# BMW_E34_Start-Stop_Btn.net
KiCad netlist of a schematic drawn in Altium Designer
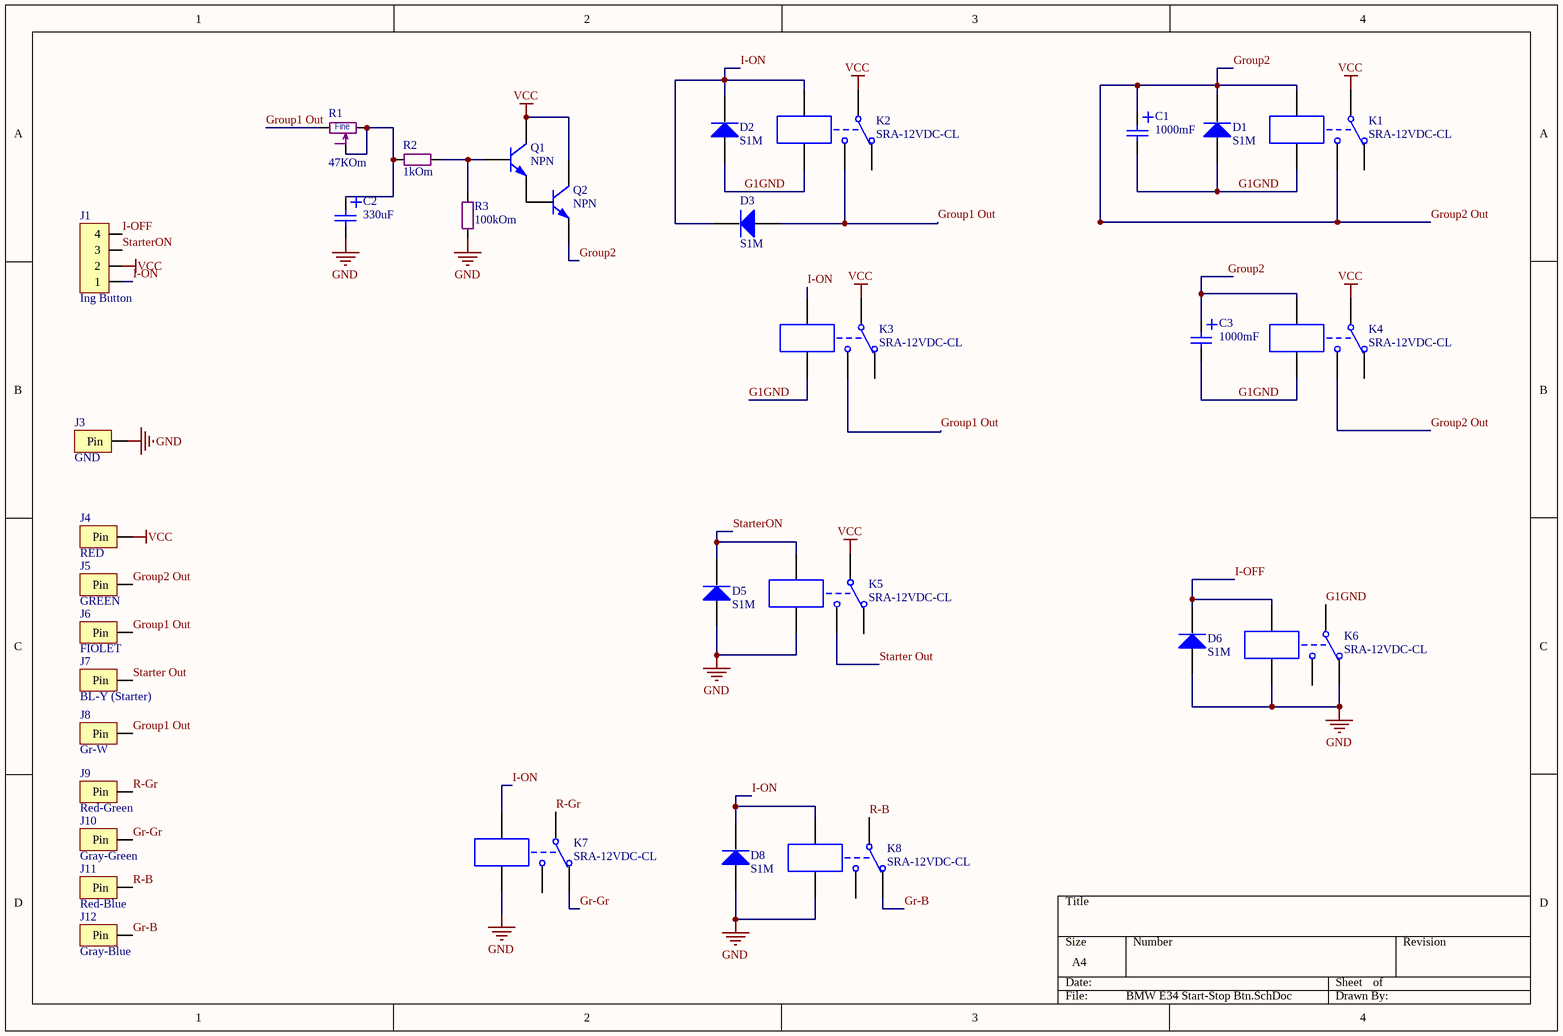
[diagram p0: BMW E34 Start-Stop Btn.SchDoc]

(export (version "E")
  (design (tool "Eeschema 10.0.6"))
  (components
    (comp (ref "C1")
      (value "1000mF")
      (footprint "Capacitor:Cap E p5.08mm D10.2mm (3p)")
      (description "Capacitor")
      (libsource (lib "Capacitor") (part "Cap E 1000mF x 25V"))
    )
    (comp (ref "C2")
      (value "330uF")
      (footprint "Capacitor:Cap E p3.5mm D8xH12")
      (description "Capacitor")
      (libsource (lib "Capacitor") (part "Cap E 470mF x 25V"))
    )
    (comp (ref "C3")
      (value "1000mF")
      (footprint "Capacitor:Cap E p5.08mm D10.2mm (3p)")
      (description "Capacitor")
      (libsource (lib "Capacitor") (part "Cap E 1000mF x 25V"))
    )
    (comp (ref "D1")
      (value "S1M")
      (footprint "Diodes:DO-214AC")
      (description "1 Amp General Purpose Rectifier")
      (libsource (lib "Diodes") (part "Diode S1M"))
    )
    (comp (ref "D2")
      (value "S1M")
      (footprint "Diodes:DO-214AC")
      (description "1 Amp General Purpose Rectifier")
      (libsource (lib "Diodes") (part "Diode S1M"))
    )
    (comp (ref "D3")
      (value "S1M")
      (footprint "Diodes:DO-214AC")
      (description "1 Amp General Purpose Rectifier")
      (libsource (lib "Diodes") (part "Diode S1M"))
    )
    (comp (ref "D5")
      (value "S1M")
      (footprint "Diodes:DO-214AC")
      (description "1 Amp General Purpose Rectifier")
      (libsource (lib "Diodes") (part "Diode S1M"))
    )
    (comp (ref "D6")
      (value "S1M")
      (footprint "Diodes:DO-214AC")
      (description "1 Amp General Purpose Rectifier")
      (libsource (lib "Diodes") (part "Diode S1M"))
    )
    (comp (ref "D8")
      (value "S1M")
      (footprint "Diodes:DO-214AC")
      (description "1 Amp General Purpose Rectifier")
      (libsource (lib "Diodes") (part "Diode S1M"))
    )
    (comp (ref "J1")
      (value "Ing Button")
      (footprint "Connector:Molex Micro-Fit 3.0 - 4 pin D R")
      (description "Horisontal, Dbl line, Male - 3mm")
      (fields (field (name "PART NUMBER") "0430450402"))
      (libsource (lib "Connector") (part "Micro-Fit 4R (2x2)"))
    )
    (comp (ref "J3")
      (value "GND")
      (footprint "Connector:OnePin 1.2x3")
      (description "Only pad")
      (libsource (lib "Connector") (part "OnePin Connector"))
    )
    (comp (ref "J4")
      (value "RED")
      (footprint "Connector:OnePin 1.5x4")
      (description "Only pad")
      (libsource (lib "Connector") (part "OnePin Connector"))
    )
    (comp (ref "J5")
      (value "GREEN")
      (footprint "Connector:OnePin 1.5x4")
      (description "Only pad")
      (libsource (lib "Connector") (part "OnePin Connector"))
    )
    (comp (ref "J6")
      (value "FIOLET")
      (footprint "Connector:OnePin 1.5x4")
      (description "Only pad")
      (libsource (lib "Connector") (part "OnePin Connector"))
    )
    (comp (ref "J7")
      (value "BL-Y (Starter)")
      (footprint "Connector:OnePin 1.5x4")
      (description "Only pad")
      (libsource (lib "Connector") (part "OnePin Connector"))
    )
    (comp (ref "J8")
      (value "Gr-W")
      (footprint "Connector:OnePin 1x2.5")
      (description "Only pad")
      (libsource (lib "Connector") (part "OnePin Connector"))
    )
    (comp (ref "J9")
      (value "Red-Green")
      (footprint "Connector:OnePin 1x2.5")
      (description "Only pad")
      (libsource (lib "Connector") (part "OnePin Connector"))
    )
    (comp (ref "J10")
      (value "Gray-Green")
      (footprint "Connector:OnePin 1x2.5")
      (description "Only pad")
      (libsource (lib "Connector") (part "OnePin Connector"))
    )
    (comp (ref "J11")
      (value "Red-Blue")
      (footprint "Connector:OnePin 1x2.5")
      (description "Only pad")
      (libsource (lib "Connector") (part "OnePin Connector"))
    )
    (comp (ref "J12")
      (value "Gray-Blue")
      (footprint "Connector:OnePin 1x2.5")
      (description "Only pad")
      (libsource (lib "Connector") (part "OnePin Connector"))
    )
    (comp (ref "K1")
      (value "SRA-12VDC-CL")
      (footprint "Relay:SRA-12VDC-CL")
      (description "Single-Pole Dual-Throw Relay")
      (libsource (lib "Relay") (part "SRA-12VDC-CL"))
    )
    (comp (ref "K2")
      (value "SRA-12VDC-CL")
      (footprint "Relay:SRA-12VDC-CL")
      (description "Single-Pole Dual-Throw Relay")
      (libsource (lib "Relay") (part "SRA-12VDC-CL"))
    )
    (comp (ref "K3")
      (value "SRA-12VDC-CL")
      (footprint "Relay:SRA-12VDC-CL")
      (description "Single-Pole Dual-Throw Relay")
      (libsource (lib "Relay") (part "SRA-12VDC-CL"))
    )
    (comp (ref "K4")
      (value "SRA-12VDC-CL")
      (footprint "Relay:SRA-12VDC-CL")
      (description "Single-Pole Dual-Throw Relay")
      (libsource (lib "Relay") (part "SRA-12VDC-CL"))
    )
    (comp (ref "K5")
      (value "SRA-12VDC-CL")
      (footprint "Relay:SRA-12VDC-CL")
      (description "Single-Pole Dual-Throw Relay")
      (libsource (lib "Relay") (part "SRA-12VDC-CL"))
    )
    (comp (ref "K6")
      (value "SRA-12VDC-CL")
      (footprint "Relay:SRA-12VDC-CL")
      (description "Single-Pole Dual-Throw Relay")
      (libsource (lib "Relay") (part "SRA-12VDC-CL"))
    )
    (comp (ref "K7")
      (value "SRA-12VDC-CL")
      (footprint "Relay:SRA-12VDC-CL")
      (description "Single-Pole Dual-Throw Relay")
      (libsource (lib "Relay") (part "SRA-12VDC-CL"))
    )
    (comp (ref "K8")
      (value "SRA-12VDC-CL")
      (footprint "Relay:SRA-12VDC-CL")
      (description "Single-Pole Dual-Throw Relay")
      (libsource (lib "Relay") (part "SRA-12VDC-CL"))
    )
    (comp (ref "Q1")
      (value "NPN")
      (footprint "GeneralCases:TO-92 2.54 (EBC)")
      (description "NPN Bipolar Transistor")
      (fields (field (name "PUBLISHER") "Altium Limited"))
      (libsource (lib "Transistor") (part "NPN"))
    )
    (comp (ref "Q2")
      (value "NPN")
      (footprint "GeneralCases:TO-92 2.54 (EBC)")
      (description "NPN Bipolar Transistor")
      (fields (field (name "PUBLISHER") "Altium Limited"))
      (libsource (lib "Transistor") (part "NPN"))
    )
    (comp (ref "R1")
      (value "47КOm")
      (footprint "PassiveComponents:Res Adj 3296 Univ")
      (libsource (lib "PassiveComponents") (part "Res Adj 3296"))
    )
    (comp (ref "R2")
      (value "1kOm")
      (footprint "PassiveComponents:SMD 0805 (2012)")
      (libsource (lib "PassiveComponents") (part "Res SMD 0805"))
    )
    (comp (ref "R3")
      (value "100kOm")
      (footprint "PassiveComponents:SMD 0805 (2012)")
      (libsource (lib "PassiveComponents") (part "Res SMD 0805"))
    )
  )
  (nets
    (net (code "1") (name "/G1GND") (class "Default")
      (node (ref "C1") (pin "2") (pinfunction "2_2") (pintype "passive"))
      (node (ref "C3") (pin "2") (pinfunction "2_2") (pintype "passive"))
      (node (ref "D1") (pin "A") (pinfunction "A_A") (pintype "passive"))
      (node (ref "D2") (pin "A") (pinfunction "A_A") (pintype "passive"))
      (node (ref "K1") (pin "5") (pinfunction "5_5") (pintype "passive"))
      (node (ref "K2") (pin "5") (pinfunction "5_5") (pintype "passive"))
      (node (ref "K3") (pin "5") (pinfunction "5_5") (pintype "passive"))
      (node (ref "K4") (pin "5") (pinfunction "5_5") (pintype "passive"))
      (node (ref "K6") (pin "2") (pinfunction "2_2") (pintype "passive"))
    )
    (net (code "2") (name "/Gr-B") (class "Default")
      (node (ref "J12") (pin "1") (pinfunction "Pin_1") (pintype "passive"))
      (node (ref "K8") (pin "1") (pinfunction "1_1") (pintype "passive"))
    )
    (net (code "3") (name "/Gr-Gr") (class "Default")
      (node (ref "J10") (pin "1") (pinfunction "Pin_1") (pintype "passive"))
      (node (ref "K7") (pin "1") (pinfunction "1_1") (pintype "passive"))
    )
    (net (code "4") (name "/Group1 Out") (class "Default")
      (node (ref "D3") (pin "A") (pinfunction "A_A") (pintype "passive"))
      (node (ref "J6") (pin "1") (pinfunction "Pin_1") (pintype "passive"))
      (node (ref "J8") (pin "1") (pinfunction "Pin_1") (pintype "passive"))
      (node (ref "K2") (pin "3") (pinfunction "3_3") (pintype "passive"))
      (node (ref "K3") (pin "3") (pinfunction "3_3") (pintype "passive"))
      (node (ref "R1") (pin "1") (pinfunction "1_1") (pintype "passive"))
    )
    (net (code "5") (name "/Group2") (class "Default")
      (node (ref "C1") (pin "1") (pinfunction "1_1") (pintype "passive"))
      (node (ref "C3") (pin "1") (pinfunction "1_1") (pintype "passive"))
      (node (ref "D1") (pin "K") (pinfunction "K_K") (pintype "passive"))
      (node (ref "J5") (pin "1") (pinfunction "Pin_1") (pintype "passive"))
      (node (ref "K1") (pin "3") (pinfunction "3_3") (pintype "passive"))
      (node (ref "K1") (pin "4") (pinfunction "4_4") (pintype "passive"))
      (node (ref "K4") (pin "3") (pinfunction "3_3") (pintype "passive"))
      (node (ref "K4") (pin "4") (pinfunction "4_4") (pintype "passive"))
      (node (ref "Q2") (pin "E") (pinfunction "E_E") (pintype "passive"))
    )
    (net (code "6") (name "/I-OFF") (class "Default")
      (node (ref "D6") (pin "K") (pinfunction "K_K") (pintype "passive"))
      (node (ref "J1") (pin "4") (pinfunction "4_4") (pintype "passive"))
      (node (ref "K6") (pin "4") (pinfunction "4_4") (pintype "passive"))
    )
    (net (code "7") (name "/I-ON") (class "Default")
      (node (ref "D2") (pin "K") (pinfunction "K_K") (pintype "passive"))
      (node (ref "D3") (pin "K") (pinfunction "K_K") (pintype "passive"))
      (node (ref "D8") (pin "K") (pinfunction "K_K") (pintype "passive"))
      (node (ref "J1") (pin "1") (pinfunction "1_1") (pintype "passive"))
      (node (ref "K2") (pin "4") (pinfunction "4_4") (pintype "passive"))
      (node (ref "K3") (pin "4") (pinfunction "4_4") (pintype "passive"))
      (node (ref "K7") (pin "4") (pinfunction "4_4") (pintype "passive"))
      (node (ref "K8") (pin "4") (pinfunction "4_4") (pintype "passive"))
    )
    (net (code "8") (name "/R-B") (class "Default")
      (node (ref "J11") (pin "1") (pinfunction "Pin_1") (pintype "passive"))
      (node (ref "K8") (pin "2") (pinfunction "2_2") (pintype "passive"))
    )
    (net (code "9") (name "/R-Gr") (class "Default")
      (node (ref "J9") (pin "1") (pinfunction "Pin_1") (pintype "passive"))
      (node (ref "K7") (pin "2") (pinfunction "2_2") (pintype "passive"))
    )
    (net (code "10") (name "/Starter Out") (class "Default")
      (node (ref "J7") (pin "1") (pinfunction "Pin_1") (pintype "passive"))
      (node (ref "K5") (pin "3") (pinfunction "3_3") (pintype "passive"))
    )
    (net (code "11") (name "/StarterON") (class "Default")
      (node (ref "D5") (pin "K") (pinfunction "K_K") (pintype "passive"))
      (node (ref "J1") (pin "3") (pinfunction "3_3") (pintype "passive"))
      (node (ref "K5") (pin "4") (pinfunction "4_4") (pintype "passive"))
    )
    (net (code "12") (name "GND") (class "Default")
      (node (ref "C2") (pin "2") (pinfunction "2_2") (pintype "passive"))
      (node (ref "D5") (pin "A") (pinfunction "A_A") (pintype "passive"))
      (node (ref "D6") (pin "A") (pinfunction "A_A") (pintype "passive"))
      (node (ref "D8") (pin "A") (pinfunction "A_A") (pintype "passive"))
      (node (ref "J3") (pin "1") (pinfunction "Pin_1") (pintype "passive"))
      (node (ref "K5") (pin "5") (pinfunction "5_5") (pintype "passive"))
      (node (ref "K6") (pin "1") (pinfunction "1_1") (pintype "passive"))
      (node (ref "K6") (pin "5") (pinfunction "5_5") (pintype "passive"))
      (node (ref "K7") (pin "5") (pinfunction "5_5") (pintype "passive"))
      (node (ref "K8") (pin "5") (pinfunction "5_5") (pintype "passive"))
      (node (ref "R3") (pin "2") (pinfunction "2_2") (pintype "passive"))
    )
    (net (code "13") (name "Net-(C2-Pad1)") (class "Default")
      (node (ref "C2") (pin "1") (pinfunction "1_1") (pintype "passive"))
      (node (ref "R1") (pin "2") (pinfunction "2_2") (pintype "passive"))
      (node (ref "R1") (pin "3") (pinfunction "3_3") (pintype "passive"))
      (node (ref "R2") (pin "2") (pinfunction "2_2") (pintype "passive"))
    )
    (net (code "14") (name "Net-(Q1-PadB)") (class "Default")
      (node (ref "Q1") (pin "B") (pinfunction "B_B") (pintype "passive"))
      (node (ref "R2") (pin "1") (pinfunction "1_1") (pintype "passive"))
      (node (ref "R3") (pin "1") (pinfunction "1_1") (pintype "passive"))
    )
    (net (code "15") (name "Net-(Q1-PadE)") (class "Default")
      (node (ref "Q1") (pin "E") (pinfunction "E_E") (pintype "passive"))
      (node (ref "Q2") (pin "B") (pinfunction "B_B") (pintype "passive"))
    )
    (net (code "16") (name "VCC") (class "Default")
      (node (ref "J1") (pin "2") (pinfunction "2_2") (pintype "passive"))
      (node (ref "J4") (pin "1") (pinfunction "Pin_1") (pintype "passive"))
      (node (ref "K1") (pin "2") (pinfunction "2_2") (pintype "passive"))
      (node (ref "K2") (pin "2") (pinfunction "2_2") (pintype "passive"))
      (node (ref "K3") (pin "2") (pinfunction "2_2") (pintype "passive"))
      (node (ref "K4") (pin "2") (pinfunction "2_2") (pintype "passive"))
      (node (ref "K5") (pin "2") (pinfunction "2_2") (pintype "passive"))
      (node (ref "Q1") (pin "C") (pinfunction "C_C") (pintype "passive"))
      (node (ref "Q2") (pin "C") (pinfunction "C_C") (pintype "passive"))
    )
    (net (code "17") (name "unconnected-(K1-Pad1)") (class "Default")
      (node (ref "K1") (pin "1") (pinfunction "1_1") (pintype "passive"))
    )
    (net (code "18") (name "unconnected-(K2-Pad1)") (class "Default")
      (node (ref "K2") (pin "1") (pinfunction "1_1") (pintype "passive"))
    )
    (net (code "19") (name "unconnected-(K3-Pad1)") (class "Default")
      (node (ref "K3") (pin "1") (pinfunction "1_1") (pintype "passive"))
    )
    (net (code "20") (name "unconnected-(K4-Pad1)") (class "Default")
      (node (ref "K4") (pin "1") (pinfunction "1_1") (pintype "passive"))
    )
    (net (code "21") (name "unconnected-(K5-Pad1)") (class "Default")
      (node (ref "K5") (pin "1") (pinfunction "1_1") (pintype "passive"))
    )
    (net (code "22") (name "unconnected-(K6-Pad3)") (class "Default")
      (node (ref "K6") (pin "3") (pinfunction "3_3") (pintype "passive"))
    )
    (net (code "23") (name "unconnected-(K7-Pad3)") (class "Default")
      (node (ref "K7") (pin "3") (pinfunction "3_3") (pintype "passive"))
    )
    (net (code "24") (name "unconnected-(K8-Pad3)") (class "Default")
      (node (ref "K8") (pin "3") (pinfunction "3_3") (pintype "passive"))
    )
  )
)
